# Drogue_Pyro.net
KiCad netlist of a schematic drawn in Altium Designer
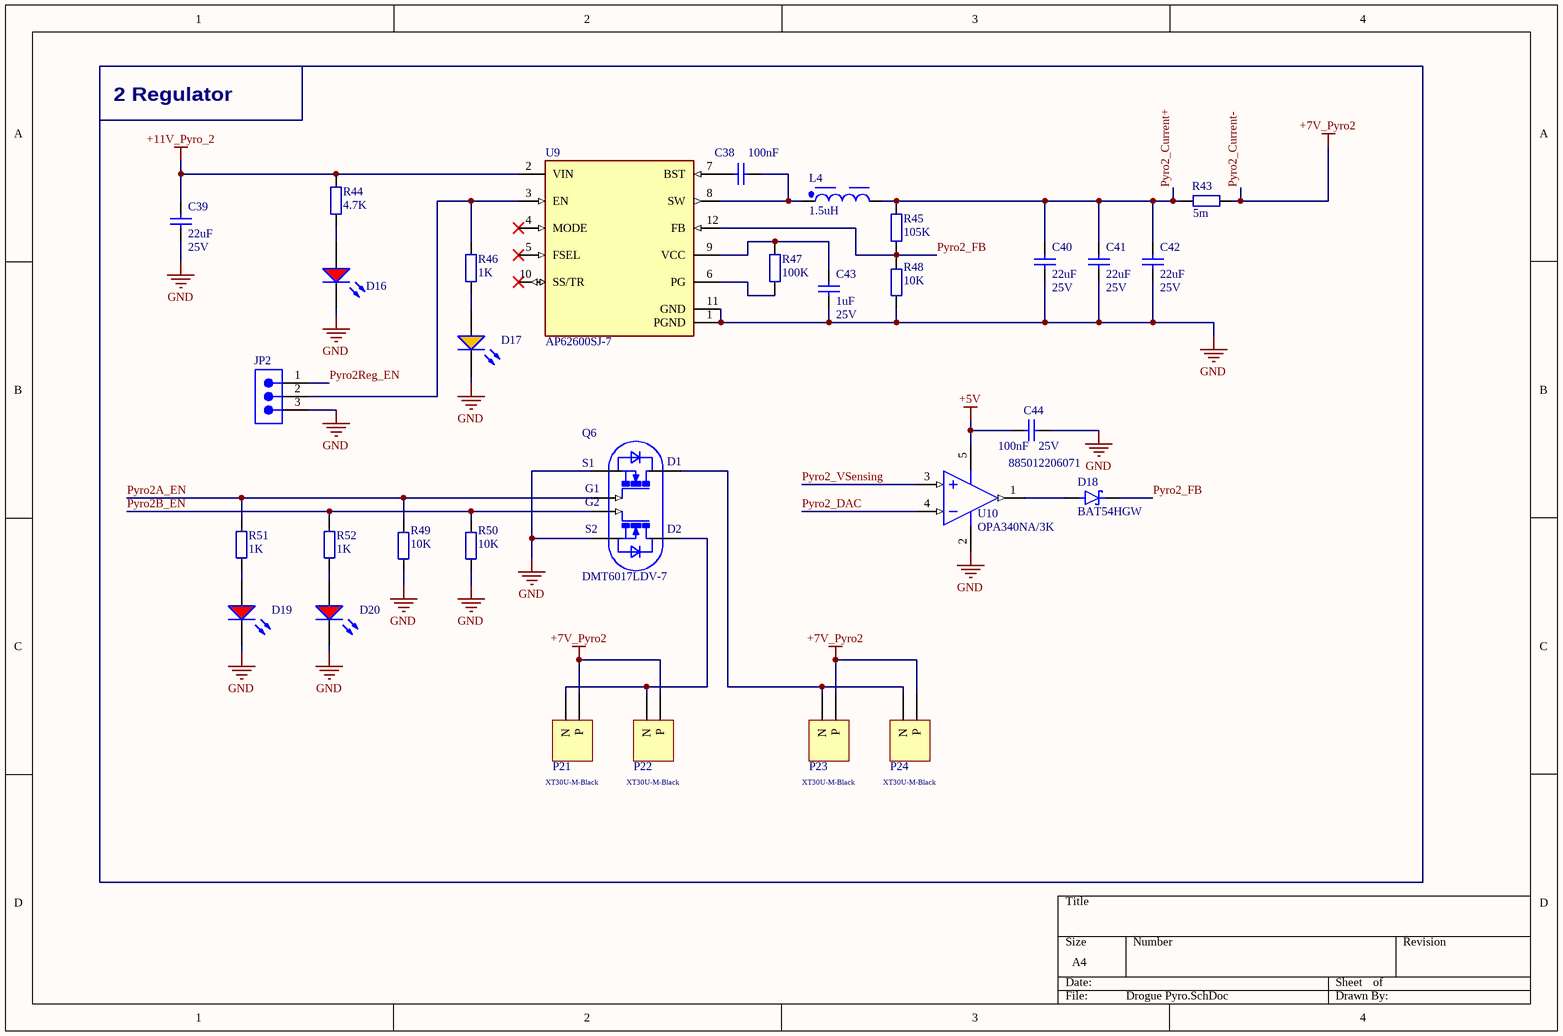
[diagram p0: Drogue Pyro.SchDoc]

(export (version "E")
  (design (tool "Eeschema 10.0.6"))
  (components
    (comp (ref "C38")
      (value "100nF")
      (footprint "MY_0603")
      (description "Capacitor, 100nF, 0603, 25V")
      (fields (field (name "VOLTAGE") "25V") (field (name "MANUFACTURER") "Wurth Elektronik"))
      (libsource (lib "LEEM UPM") (part "Cap ceramic"))
    )
    (comp (ref "C39")
      (value "22uF")
      (footprint "MY_0805")
      (description "Capacitor, 22uF, 0805, 25V")
      (fields
        (field (name "MANUFACTURER") "Samsung")
        (field (name "MANUFACTURER PART NUMBER") "CL21A226MAYNNNE")
        (field (name "VOLTAGE") "25V")
      )
      (libsource (lib "LEEM UPM") (part "Cap ceramic"))
    )
    (comp (ref "C40")
      (value "22uF")
      (footprint "MY_0805")
      (description "Capacitor, 22uF, 0805, 25V")
      (fields
        (field (name "MANUFACTURER") "Samsung")
        (field (name "MANUFACTURER PART NUMBER") "CL21A226MAYNNNE")
        (field (name "VOLTAGE") "25V")
      )
      (libsource (lib "LEEM UPM") (part "Cap ceramic"))
    )
    (comp (ref "C41")
      (value "22uF")
      (footprint "MY_0805")
      (description "Capacitor, 22uF, 0805, 25V")
      (fields
        (field (name "MANUFACTURER") "Samsung")
        (field (name "MANUFACTURER PART NUMBER") "CL21A226MAYNNNE")
        (field (name "VOLTAGE") "25V")
      )
      (libsource (lib "LEEM UPM") (part "Cap ceramic"))
    )
    (comp (ref "C42")
      (value "22uF")
      (footprint "MY_0805")
      (description "Capacitor, 22uF, 0805, 25V")
      (fields
        (field (name "MANUFACTURER") "Samsung")
        (field (name "MANUFACTURER PART NUMBER") "CL21A226MAYNNNE")
        (field (name "VOLTAGE") "25V")
      )
      (libsource (lib "LEEM UPM") (part "Cap ceramic"))
    )
    (comp (ref "C43")
      (value "1uF")
      (footprint "MY_0603")
      (description "Capacitor, 1uF, 0603, 25V")
      (fields
        (field (name "VOLTE") "25V")
        (field (name "MANUFACTURER") "Wurth Elektronik")
        (field (name "MANUFACTURER PART NUMBER") "885012206052")
      )
      (libsource (lib "LEEM UPM") (part "Cap ceramic"))
    )
    (comp (ref "C44")
      (value "100nF")
      (footprint "MY_0603")
      (description "Capacitor, 100nF, 0603, 25V")
      (fields
        (field (name "VOLTAGE") "25V")
        (field (name "MANUFACTURER") "Wurth Elektronik")
        (field (name "MANUFACTURER PART NUMBER") "885012206071")
        (field (name "Comment") "Cap ceramic")
      )
      (libsource (lib "LEEM UPM") (part "Cap ceramic"))
    )
    (comp (ref "D16")
      (value "150080RS75000")
      (footprint "WL-SMCW_0805_150080xx75000")
      (description "LED, 0805, Red")
      (fields (field (name "MANUFACTURER") "Wurth Elektronik"))
      (libsource (lib "Altium Content Vault") (part "LED_Red_2A-1K"))
    )
    (comp (ref "D17")
      (value "150080AS75000")
      (footprint "WL-SMCW_0805_150080xx75000")
      (description "Amber")
      (fields (field (name "MANUFACTURER") "Wurth Elektronik"))
      (libsource (lib "Altium Content Vault") (part "LED_Amber_2A-1K"))
    )
    (comp (ref "D18")
      (value "BAT54HGW")
      (footprint "BAT54HGW-Footprint-1")
      (description "BAT54HGW Schotty Diode")
      (fields (field (name "MANUFACTURER") "Nexperia"))
      (libsource (lib "LEEM UPM") (part "BAT54HGW"))
    )
    (comp (ref "D19")
      (value "150080RS75000")
      (footprint "WL-SMCW_0805_150080xx75000")
      (description "LED, 0805, Red")
      (fields (field (name "MANUFACTURER") "Wurth Elektronik"))
      (libsource (lib "Altium Content Vault") (part "LED_Red_2A-1K"))
    )
    (comp (ref "D20")
      (value "150080RS75000")
      (footprint "WL-SMCW_0805_150080xx75000")
      (description "LED, 0805, Red")
      (fields (field (name "MANUFACTURER") "Wurth Elektronik"))
      (libsource (lib "Altium Content Vault") (part "LED_Red_2A-1K"))
    )
    (comp (ref "JP2")
      (value "Jumper 3 pin, 2,54mm")
      (footprint "Jumper 3 pin, 2,54mm-Footprint-1")
      (libsource (lib "LEEM UPM") (part "New symbol 1"))
    )
    (comp (ref "L4")
      (value "1.5uH")
      (footprint "WE-MAPI_4020")
      (description "74438356015 Fixed Ind 1.5UH 5.8A 19 Mohm SMD")
      (fields
        (field (name "MANUFACTURER") "Wurth Elektronik")
        (field (name "MANUFACTURER PART NUMBER") "74438356015")
      )
      (libsource (lib "Altium Content Vault") (part "Inductor - 2"))
    )
    (comp (ref "P21")
      (value "XT30U-M-Black")
      (footprint "XT30-Footprint-2")
      (description "XT30PW-M公头 Socket,DCsupply,XT30,male,PIN:2")
      (fields (field (name "MANUFACTURER") "AMASS"))
      (libsource (lib "LEEM UPM") (part "XT30PW"))
    )
    (comp (ref "P22")
      (value "XT30U-M-Black")
      (footprint "XT30-Footprint-2")
      (description "XT30PW-M公头 Socket,DCsupply,XT30,male,PIN:2")
      (fields (field (name "MANUFACTURER") "AMASS"))
      (libsource (lib "LEEM UPM") (part "XT30PW"))
    )
    (comp (ref "P23")
      (value "XT30U-M-Black")
      (footprint "XT30-Footprint-2")
      (description "XT30PW-M公头 Socket,DCsupply,XT30,male,PIN:2")
      (fields (field (name "MANUFACTURER") "AMASS"))
      (libsource (lib "LEEM UPM") (part "XT30PW"))
    )
    (comp (ref "P24")
      (value "XT30U-M-Black")
      (footprint "XT30-Footprint-2")
      (description "XT30PW-M公头 Socket,DCsupply,XT30,male,PIN:2")
      (fields (field (name "MANUFACTURER") "AMASS"))
      (libsource (lib "LEEM UPM") (part "XT30PW"))
    )
    (comp (ref "Q6")
      (value "DMT6017LDV-7")
      (footprint "DMT6017LDV-7-Footprint-1")
      (description "Small Signal Field-Effect Transistor")
      (libsource (lib "LEEM UPM") (part "DMT6017LDV"))
    )
    (comp (ref "R43")
      (value "5m")
      (footprint "R0612")
      (description "Resistor, 5m, 0612, 2W")
      (fields
        (field (name "MANUFACTURER") "Vishay")
        (field (name "MANUFACTURER PART NUMBER") "WFCP06125L000FE66")
      )
      (libsource (lib "LEEM UPM") (part "RK73H2ALTD1004F"))
    )
    (comp (ref "R44")
      (value "4.7K")
      (footprint "R0603-0.45")
      (description "Resistor, 4.7K, 0603, 0.1W")
      (fields (field (name "MANUFACTURER") "Wurth") (field (name "MANUFACTURER PART NUMBER") "560112116006"))
      (libsource (lib "LEEM UPM") (part "RK73H2ALTD1004F"))
    )
    (comp (ref "R45")
      (value "105K")
      (footprint "R0603-0.45")
      (description "Resistor, 105K, 0603, 0.1W")
      (fields (field (name "MANUFACTURER") "Wurth") (field (name "MANUFACTURER PART NUMBER") "560112110183"))
      (libsource (lib "IFS_Altium") (part "R"))
    )
    (comp (ref "R46")
      (value "1K")
      (footprint "R0603-0.45")
      (description "Resistor, 1K, 0603, 0.1W")
      (fields (field (name "MANUFACTURER") "Wurth") (field (name "MANUFACTURER PART NUMBER") "560112116014"))
      (libsource (lib "LEEM UPM") (part "RK73H2ALTD1004F"))
    )
    (comp (ref "R47")
      (value "100K")
      (footprint "R0603-0.45")
      (description "Resistor, 100K, 0603, 0.1W")
      (fields (field (name "MANUFACTURER") "Wurth") (field (name "MANUFACTURER PART NUMBER") "560112116004"))
      (libsource (lib "IFS_Altium") (part "R"))
    )
    (comp (ref "R48")
      (value "10K")
      (footprint "R0603-0.45")
      (description "Resistor, 10K, 0603, 0.1W")
      (fields (field (name "MANUFACTURER") "Wurth") (field (name "MANUFACTURER PART NUMBER") "560112116005"))
      (libsource (lib "IFS_Altium") (part "R"))
    )
    (comp (ref "R49")
      (value "10K")
      (footprint "R0603-0.45")
      (description "Resistor, 10K, 0603, 0.1W")
      (fields (field (name "MANUFACTURER") "Wurth") (field (name "MANUFACTURER PART NUMBER") "560112116005"))
      (libsource (lib "IFS_Altium") (part "R"))
    )
    (comp (ref "R50")
      (value "10K")
      (footprint "R0603-0.45")
      (description "Resistor, 10K, 0603, 0.1W")
      (fields (field (name "MANUFACTURER") "Wurth") (field (name "MANUFACTURER PART NUMBER") "560112116005"))
      (libsource (lib "IFS_Altium") (part "R"))
    )
    (comp (ref "R51")
      (value "1K")
      (footprint "R0603-0.45")
      (description "Resistor, 1K, 0603, 0.1W")
      (fields (field (name "MANUFACTURER") "Wurth") (field (name "MANUFACTURER PART NUMBER") "560112116014"))
      (libsource (lib "LEEM UPM") (part "RK73H2ALTD1004F"))
    )
    (comp (ref "R52")
      (value "1K")
      (footprint "R0603-0.45")
      (description "Resistor, 1K, 0603, 0.1W")
      (fields (field (name "MANUFACTURER") "Wurth") (field (name "MANUFACTURER PART NUMBER") "560112116014"))
      (libsource (lib "LEEM UPM") (part "RK73H2ALTD1004F"))
    )
    (comp (ref "U9")
      (value "AP62600SJ-7")
      (footprint "FP-V-QFN2030-12_Type_A-MFG")
      (description "Switching Regulator, 1200kHz Switching Freq-Max")
      (fields (field (name "MANUFACTURER") "Diodes Incorporated"))
      (libsource (lib "LEEM UPM") (part "03c86ce2703f4b33b3045e94f7be521"))
    )
    (comp (ref "U10")
      (value "OPA340NA/3K")
      (footprint "DBV0005A_M")
      (libsource (lib "Altium Content Vault") (part "TI-OPA_SM7XXXX-DBV5"))
    )
  )
  (nets
    (net (code "1") (name "+5V") (class "Default")
      (node (ref "C44") (pin "2") (pinfunction "2_2") (pintype "passive"))
      (node (ref "U10") (pin "5") (pinfunction "V+_5") (pintype "power_in"))
    )
    (net (code "2") (name "+7V_Pyro2") (class "Default")
      (node (ref "P21") (pin "P") (pinfunction "P_P") (pintype "passive"))
      (node (ref "P22") (pin "P") (pinfunction "P_P") (pintype "passive"))
      (node (ref "P23") (pin "P") (pinfunction "P_P") (pintype "passive"))
      (node (ref "P24") (pin "P") (pinfunction "P_P") (pintype "passive"))
      (node (ref "R43") (pin "2") (pinfunction "2_2") (pintype "passive"))
    )
    (net (code "3") (name "+11V_Pyro_2") (class "Default")
      (node (ref "C39") (pin "1") (pinfunction "1_1") (pintype "passive"))
      (node (ref "R44") (pin "2") (pinfunction "2_2") (pintype "passive"))
      (node (ref "U9") (pin "2") (pinfunction "VIN_2") (pintype "power_in"))
    )
    (net (code "5") (name "/Pyro2A_EN") (class "Default")
      (node (ref "Q6") (pin "2") (pinfunction "G1_2") (pintype "input"))
      (node (ref "R49") (pin "1") (pinfunction "1_1") (pintype "passive"))
      (node (ref "R51") (pin "2") (pinfunction "2_2") (pintype "passive"))
    )
    (net (code "6") (name "/Pyro2B_EN") (class "Default")
      (node (ref "Q6") (pin "4") (pinfunction "G2_4") (pintype "input"))
      (node (ref "R50") (pin "1") (pinfunction "1_1") (pintype "passive"))
      (node (ref "R52") (pin "2") (pinfunction "2_2") (pintype "passive"))
    )
    (net (code "7") (name "/Pyro2Reg_EN") (class "Default")
      (node (ref "JP2") (pin "1") (pinfunction "1_1") (pintype "passive"))
    )
    (net (code "8") (name "/Pyro2_Current+") (class "Default")
      (node (ref "C40") (pin "1") (pinfunction "1_1") (pintype "passive"))
      (node (ref "C41") (pin "1") (pinfunction "1_1") (pintype "passive"))
      (node (ref "C42") (pin "1") (pinfunction "1_1") (pintype "passive"))
      (node (ref "L4") (pin "2") (pinfunction "2_2") (pintype "passive"))
      (node (ref "R43") (pin "1") (pinfunction "1_1") (pintype "passive"))
      (node (ref "R45") (pin "1") (pinfunction "1_1") (pintype "passive"))
    )
    (net (code "9") (name "/Pyro2_DAC") (class "Default")
      (node (ref "U10") (pin "4") (pinfunction "IN-_4") (pintype "input"))
    )
    (net (code "10") (name "/Pyro2_FB") (class "Default")
      (node (ref "D18") (pin "C") (pinfunction "K_C") (pintype "passive"))
      (node (ref "R45") (pin "2") (pinfunction "2_2") (pintype "passive"))
      (node (ref "R48") (pin "1") (pinfunction "1_1") (pintype "passive"))
      (node (ref "U9") (pin "12") (pinfunction "FB_12") (pintype "input"))
    )
    (net (code "11") (name "/Pyro2_VSensing") (class "Default")
      (node (ref "U10") (pin "3") (pinfunction "IN+_3") (pintype "input"))
    )
    (net (code "12") (name "GND") (class "Default")
      (node (ref "C39") (pin "2") (pinfunction "2_2") (pintype "passive"))
      (node (ref "C40") (pin "2") (pinfunction "2_2") (pintype "passive"))
      (node (ref "C41") (pin "2") (pinfunction "2_2") (pintype "passive"))
      (node (ref "C42") (pin "2") (pinfunction "2_2") (pintype "passive"))
      (node (ref "C43") (pin "1") (pinfunction "1_1") (pintype "passive"))
      (node (ref "C44") (pin "1") (pinfunction "1_1") (pintype "passive"))
      (node (ref "D16") (pin "1") (pinfunction "K_1") (pintype "passive"))
      (node (ref "D17") (pin "1") (pinfunction "K_1") (pintype "passive"))
      (node (ref "D19") (pin "1") (pinfunction "K_1") (pintype "passive"))
      (node (ref "D20") (pin "1") (pinfunction "K_1") (pintype "passive"))
      (node (ref "JP2") (pin "3") (pinfunction "3_3") (pintype "passive"))
      (node (ref "Q6") (pin "1") (pinfunction "S1_1") (pintype "power_in"))
      (node (ref "Q6") (pin "3") (pinfunction "S2_3") (pintype "power_in"))
      (node (ref "R48") (pin "2") (pinfunction "2_2") (pintype "passive"))
      (node (ref "R49") (pin "2") (pinfunction "2_2") (pintype "passive"))
      (node (ref "R50") (pin "2") (pinfunction "2_2") (pintype "passive"))
      (node (ref "U10") (pin "2") (pinfunction "V-_2") (pintype "power_in"))
      (node (ref "U9") (pin "1") (pinfunction "PGND_1") (pintype "power_in"))
      (node (ref "U9") (pin "11") (pinfunction "GND_11") (pintype "power_in"))
    )
    (net (code "13") (name "Net-(D16-A)") (class "Default")
      (node (ref "D16") (pin "2") (pinfunction "A_2") (pintype "passive"))
      (node (ref "R44") (pin "1") (pinfunction "1_1") (pintype "passive"))
    )
    (net (code "14") (name "Net-(D17-A)") (class "Default")
      (node (ref "D17") (pin "2") (pinfunction "A_2") (pintype "passive"))
      (node (ref "R46") (pin "1") (pinfunction "1_1") (pintype "passive"))
    )
    (net (code "15") (name "Net-(D19-A)") (class "Default")
      (node (ref "D19") (pin "2") (pinfunction "A_2") (pintype "passive"))
      (node (ref "R51") (pin "1") (pinfunction "1_1") (pintype "passive"))
    )
    (net (code "16") (name "Net-(D20-A)") (class "Default")
      (node (ref "D20") (pin "2") (pinfunction "A_2") (pintype "passive"))
      (node (ref "R52") (pin "1") (pinfunction "1_1") (pintype "passive"))
    )
    (net (code "17") (name "Net-(Q6-D1)") (class "Default")
      (node (ref "P23") (pin "N") (pinfunction "N_N") (pintype "passive"))
      (node (ref "P24") (pin "N") (pinfunction "N_N") (pintype "passive"))
      (node (ref "Q6") (pin "8") (pinfunction "D1_8") (pintype "power_in"))
    )
    (net (code "18") (name "Net-(Q6-D2)") (class "Default")
      (node (ref "P21") (pin "N") (pinfunction "N_N") (pintype "passive"))
      (node (ref "P22") (pin "N") (pinfunction "N_N") (pintype "passive"))
      (node (ref "Q6") (pin "6") (pinfunction "D2_6") (pintype "power_in"))
    )
    (net (code "19") (name "Net-(U9-BST)") (class "Default")
      (node (ref "C38") (pin "2") (pinfunction "2_2") (pintype "passive"))
      (node (ref "U9") (pin "7") (pinfunction "BST_7") (pintype "input"))
    )
    (net (code "20") (name "Net-(U9-EN)") (class "Default")
      (node (ref "JP2") (pin "2") (pinfunction "2_2") (pintype "passive"))
      (node (ref "R46") (pin "2") (pinfunction "2_2") (pintype "passive"))
      (node (ref "U9") (pin "3") (pinfunction "EN_3") (pintype "input"))
    )
    (net (code "21") (name "Net-(U9-PG)") (class "Default")
      (node (ref "R47") (pin "2") (pinfunction "2_2") (pintype "passive"))
      (node (ref "U9") (pin "6") (pinfunction "PG_6") (pintype "open_collector"))
    )
    (net (code "22") (name "Net-(U9-SW)") (class "Default")
      (node (ref "C38") (pin "1") (pinfunction "1_1") (pintype "passive"))
      (node (ref "L4") (pin "1") (pinfunction "1_1") (pintype "passive"))
      (node (ref "U9") (pin "8") (pinfunction "SW_8") (pintype "output"))
    )
    (net (code "23") (name "Net-(U9-VCC)") (class "Default")
      (node (ref "C43") (pin "2") (pinfunction "2_2") (pintype "passive"))
      (node (ref "R47") (pin "1") (pinfunction "1_1") (pintype "passive"))
      (node (ref "U9") (pin "9") (pinfunction "VCC_9") (pintype "power_in"))
    )
    (net (code "24") (name "Net-(U10-OUT)") (class "Default")
      (node (ref "D18") (pin "A") (pinfunction "A_A") (pintype "passive"))
      (node (ref "U10") (pin "1") (pinfunction "OUT_1") (pintype "output"))
    )
    (net (code "25") (name "unconnected-(U9-FSEL-Pad5)") (class "Default")
      (node (ref "U9") (pin "5") (pinfunction "FSEL_5") (pintype "input+no_connect"))
    )
    (net (code "26") (name "unconnected-(U9-MODE-Pad4)") (class "Default")
      (node (ref "U9") (pin "4") (pinfunction "MODE_4") (pintype "input+no_connect"))
    )
    (net (code "27") (name "unconnected-(U9-SS{slash}TR-Pad10)") (class "Default")
      (node (ref "U9") (pin "10") (pinfunction "SS/TR_10") (pintype "bidirectional+no_connect"))
    )
  )
)
